# ME433_Spring2017.net
KiCad netlist of a schematic drawn in EAGLE
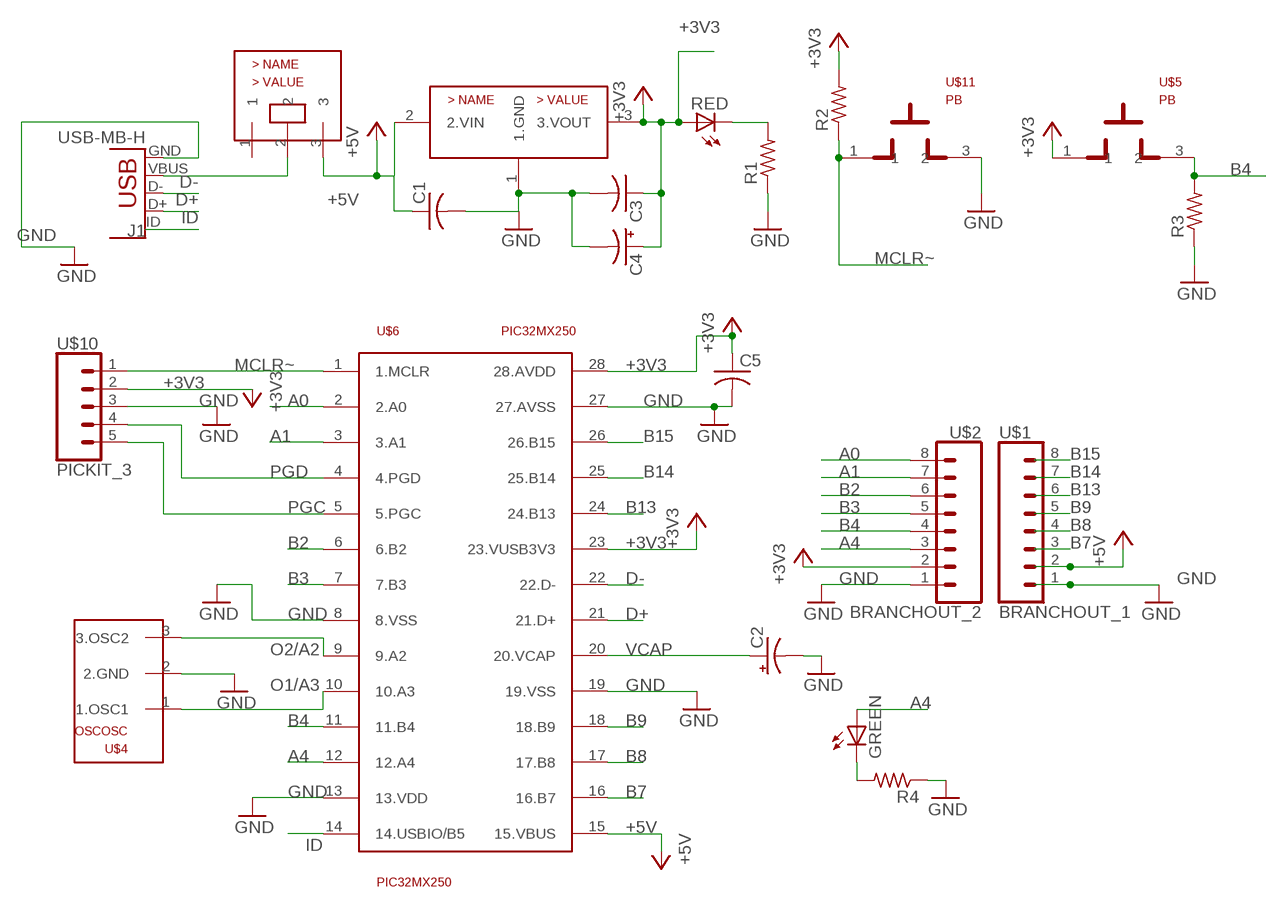
[diagram p0: schematic, sheet 1]

(export (version "E")
  (design (tool "Eeschema 10.0.6"))
  (components
    (comp (ref "C1")
      (value "C-US025-025X050")
      (footprint "eagle-import:C025-025X050")
      (libsource (lib "eagle-import") (part "C-US025-025X050"))
    )
    (comp (ref "C2")
      (value "CPOL-USB45181B")
      (footprint "eagle-import:B45181B")
      (libsource (lib "eagle-import") (part "CPOL-USB45181B"))
    )
    (comp (ref "C3")
      (value "C-US025-025X050")
      (footprint "eagle-import:C025-025X050")
      (libsource (lib "eagle-import") (part "C-US025-025X050"))
    )
    (comp (ref "C4")
      (value "CPOL-USB45181B")
      (footprint "eagle-import:B45181B")
      (libsource (lib "eagle-import") (part "CPOL-USB45181B"))
    )
    (comp (ref "C5")
      (value "C-US025-025X050")
      (footprint "eagle-import:C025-025X050")
      (libsource (lib "eagle-import") (part "C-US025-025X050"))
    )
    (comp (ref "GREEN")
      (value "LED3MM")
      (footprint "eagle-import:LED3MM")
      (libsource (lib "eagle-import") (part "LED3MM"))
    )
    (comp (ref "J1")
      (value "USB-MB-H")
      (footprint "eagle-import:USB-MB-H")
      (libsource (lib "eagle-import") (part "USB-MB-H"))
    )
    (comp (ref "R1")
      (value "R-US_0204/7")
      (footprint "eagle-import:0204_7")
      (libsource (lib "eagle-import") (part "R-US_0204/7"))
    )
    (comp (ref "R2")
      (value "R-US_0204/7")
      (footprint "eagle-import:0204_7")
      (libsource (lib "eagle-import") (part "R-US_0204/7"))
    )
    (comp (ref "R3")
      (value "R-US_0204/7")
      (footprint "eagle-import:0204_7")
      (libsource (lib "eagle-import") (part "R-US_0204/7"))
    )
    (comp (ref "R4")
      (value "R-US_0204/7")
      (footprint "eagle-import:0204_7")
      (libsource (lib "eagle-import") (part "R-US_0204/7"))
    )
    (comp (ref "RED")
      (value "LED3MM")
      (footprint "eagle-import:LED3MM")
      (libsource (lib "eagle-import") (part "LED3MM"))
    )
    (comp (ref "U$1")
      (value "BRANCHOUT_1")
      (footprint "eagle-import:1X08")
      (libsource (lib "eagle-import") (part "BRANCHOUT_1"))
    )
    (comp (ref "U$2")
      (value "BRANCHOUT_2")
      (footprint "eagle-import:1X08")
      (libsource (lib "eagle-import") (part "BRANCHOUT_2"))
    )
    (comp (ref "U$4")
      (value "OSCOSC")
      (footprint "eagle-import:OSC")
      (libsource (lib "eagle-import") (part "OSCOSC"))
    )
    (comp (ref "U$5") (value "PB") (footprint "eagle-import:PB") (libsource (lib "eagle-import") (part "PB")))
    (comp (ref "U$6")
      (value "PIC32MX250")
      (footprint "eagle-import:DIL28-3")
      (libsource (lib "eagle-import") (part "PIC32MX250"))
    )
    (comp (ref "U$8")
      (value "SLIDE")
      (footprint "eagle-import:SLIDE")
      (libsource (lib "eagle-import") (part "SLIDE"))
    )
    (comp (ref "U$10")
      (value "PICKIT_3")
      (footprint "eagle-import:1X05")
      (libsource (lib "eagle-import") (part "PICKIT_3"))
    )
    (comp (ref "U$11")
      (value "PB")
      (footprint "eagle-import:PB")
      (libsource (lib "eagle-import") (part "PB"))
    )
    (comp (ref "_")
      (value "MCP1702")
      (footprint "eagle-import:TO92")
      (libsource (lib "eagle-import") (part "MCP1702"))
    )
  )
  (nets
    (net (code "1") (name "+3V3") (class "Default")
      (node (ref "C3") (pin "1") (pinfunction "1_1") (pintype "passive"))
      (node (ref "C4") (pin "+") (pinfunction "+_+") (pintype "passive"))
      (node (ref "C5") (pin "1") (pinfunction "1_1") (pintype "passive"))
      (node (ref "R2") (pin "2") (pinfunction "2_2") (pintype "passive"))
      (node (ref "RED") (pin "A") (pinfunction "A_A") (pintype "passive"))
      (node (ref "U$10") (pin "2") (pinfunction "2.VDD_2") (pintype "passive"))
      (node (ref "U$2") (pin "2") (pinfunction "2_2") (pintype "passive"))
      (node (ref "U$5") (pin "1") (pinfunction "1_1") (pintype "bidirectional"))
      (node (ref "U$6") (pin "23") (pinfunction "23.VUSB3V3_23") (pintype "bidirectional"))
      (node (ref "U$6") (pin "28") (pinfunction "28.AVDD_28") (pintype "bidirectional"))
      (node (ref "_") (pin "3") (pinfunction "3.VOUT_3") (pintype "bidirectional"))
    )
    (net (code "2") (name "+5V") (class "Default")
      (node (ref "C1") (pin "1") (pinfunction "1_1") (pintype "passive"))
      (node (ref "U$1") (pin "2") (pinfunction "2_2") (pintype "passive"))
      (node (ref "U$6") (pin "15") (pinfunction "15.VBUS_15") (pintype "bidirectional"))
      (node (ref "U$8") (pin "3") (pinfunction "3_3") (pintype "bidirectional"))
      (node (ref "_") (pin "2") (pinfunction "2.VIN_2") (pintype "bidirectional"))
    )
    (net (code "3") (name "/A0") (class "Default")
      (node (ref "U$2") (pin "8") (pinfunction "8_8") (pintype "passive"))
      (node (ref "U$6") (pin "2") (pinfunction "2.A0_2") (pintype "bidirectional"))
    )
    (net (code "4") (name "/A1") (class "Default")
      (node (ref "U$2") (pin "7") (pinfunction "7_7") (pintype "passive"))
      (node (ref "U$6") (pin "3") (pinfunction "3.A1_3") (pintype "bidirectional"))
    )
    (net (code "5") (name "/A4") (class "Default")
      (node (ref "GREEN") (pin "A") (pinfunction "A_A") (pintype "passive"))
      (node (ref "U$2") (pin "3") (pinfunction "3_3") (pintype "passive"))
      (node (ref "U$6") (pin "12") (pinfunction "12.A4_12") (pintype "bidirectional"))
    )
    (net (code "6") (name "/B2") (class "Default")
      (node (ref "U$2") (pin "6") (pinfunction "6_6") (pintype "passive"))
      (node (ref "U$6") (pin "6") (pinfunction "6.B2_6") (pintype "bidirectional"))
    )
    (net (code "7") (name "/B3") (class "Default")
      (node (ref "U$2") (pin "5") (pinfunction "5_5") (pintype "passive"))
      (node (ref "U$6") (pin "7") (pinfunction "7.B3_7") (pintype "bidirectional"))
    )
    (net (code "8") (name "/B4") (class "Default")
      (node (ref "R3") (pin "2") (pinfunction "2_2") (pintype "passive"))
      (node (ref "U$2") (pin "4") (pinfunction "4_4") (pintype "passive"))
      (node (ref "U$5") (pin "3") (pinfunction "2_3") (pintype "bidirectional"))
      (node (ref "U$6") (pin "11") (pinfunction "11.B4_11") (pintype "bidirectional"))
    )
    (net (code "9") (name "/B7") (class "Default")
      (node (ref "U$1") (pin "3") (pinfunction "3_3") (pintype "passive"))
      (node (ref "U$6") (pin "16") (pinfunction "16.B7_16") (pintype "bidirectional"))
    )
    (net (code "10") (name "/B8") (class "Default")
      (node (ref "U$1") (pin "4") (pinfunction "4_4") (pintype "passive"))
      (node (ref "U$6") (pin "17") (pinfunction "17.B8_17") (pintype "bidirectional"))
    )
    (net (code "11") (name "/B9") (class "Default")
      (node (ref "U$1") (pin "5") (pinfunction "5_5") (pintype "passive"))
      (node (ref "U$6") (pin "18") (pinfunction "18.B9_18") (pintype "bidirectional"))
    )
    (net (code "12") (name "/B13") (class "Default")
      (node (ref "U$1") (pin "6") (pinfunction "6_6") (pintype "passive"))
      (node (ref "U$6") (pin "24") (pinfunction "24.B13_24") (pintype "bidirectional"))
    )
    (net (code "13") (name "/B14") (class "Default")
      (node (ref "U$1") (pin "7") (pinfunction "7_7") (pintype "passive"))
      (node (ref "U$6") (pin "25") (pinfunction "25.B14_25") (pintype "bidirectional"))
    )
    (net (code "14") (name "/B15") (class "Default")
      (node (ref "U$1") (pin "8") (pinfunction "8_8") (pintype "passive"))
      (node (ref "U$6") (pin "26") (pinfunction "26.B15_26") (pintype "bidirectional"))
    )
    (net (code "15") (name "/D+") (class "Default")
      (node (ref "J1") (pin "D+") (pinfunction "D+_D+") (pintype "bidirectional"))
      (node (ref "U$6") (pin "21") (pinfunction "21.D+_21") (pintype "bidirectional"))
    )
    (net (code "16") (name "/D-") (class "Default")
      (node (ref "J1") (pin "D-") (pinfunction "D-_D-") (pintype "bidirectional"))
      (node (ref "U$6") (pin "22") (pinfunction "22.D-_22") (pintype "bidirectional"))
    )
    (net (code "17") (name "/ID") (class "Default")
      (node (ref "J1") (pin "ID") (pinfunction "ID_ID") (pintype "bidirectional"))
      (node (ref "U$6") (pin "14") (pinfunction "14.USBIO/B5_14") (pintype "bidirectional"))
    )
    (net (code "18") (name "/MCLR~{}") (class "Default")
      (node (ref "R2") (pin "1") (pinfunction "1_1") (pintype "passive"))
      (node (ref "U$10") (pin "1") (pinfunction "1.MCLR~{}_1") (pintype "passive"))
      (node (ref "U$11") (pin "1") (pinfunction "1_1") (pintype "bidirectional"))
      (node (ref "U$6") (pin "1") (pinfunction "1.MCLR_1") (pintype "bidirectional"))
    )
    (net (code "19") (name "/O1{slash}A3") (class "Default")
      (node (ref "U$4") (pin "1") (pinfunction "1.OSC1_1") (pintype "bidirectional"))
      (node (ref "U$6") (pin "10") (pinfunction "10.A3_10") (pintype "bidirectional"))
    )
    (net (code "20") (name "/O2{slash}A2") (class "Default")
      (node (ref "U$4") (pin "3") (pinfunction "3.OSC2_3") (pintype "bidirectional"))
      (node (ref "U$6") (pin "9") (pinfunction "9.A2_9") (pintype "bidirectional"))
    )
    (net (code "21") (name "/PGC") (class "Default")
      (node (ref "U$10") (pin "5") (pinfunction "5.PGC_5") (pintype "passive"))
      (node (ref "U$6") (pin "5") (pinfunction "5.PGC_5") (pintype "bidirectional"))
    )
    (net (code "22") (name "/PGD") (class "Default")
      (node (ref "U$10") (pin "4") (pinfunction "4.PGD_4") (pintype "passive"))
      (node (ref "U$6") (pin "4") (pinfunction "4.PGD_4") (pintype "bidirectional"))
    )
    (net (code "23") (name "/VCAP") (class "Default")
      (node (ref "C2") (pin "+") (pinfunction "+_+") (pintype "passive"))
      (node (ref "U$6") (pin "20") (pinfunction "20.VCAP_20") (pintype "bidirectional"))
    )
    (net (code "24") (name "GND") (class "Default")
      (node (ref "C1") (pin "2") (pinfunction "2_2") (pintype "passive"))
      (node (ref "C2") (pin "-") (pinfunction "-_-") (pintype "passive"))
      (node (ref "C3") (pin "2") (pinfunction "2_2") (pintype "passive"))
      (node (ref "C4") (pin "-") (pinfunction "-_-") (pintype "passive"))
      (node (ref "C5") (pin "2") (pinfunction "2_2") (pintype "passive"))
      (node (ref "J1") (pin "GND") (pinfunction "GND_GND") (pintype "bidirectional"))
      (node (ref "R1") (pin "1") (pinfunction "1_1") (pintype "passive"))
      (node (ref "R3") (pin "1") (pinfunction "1_1") (pintype "passive"))
      (node (ref "R4") (pin "1") (pinfunction "1_1") (pintype "passive"))
      (node (ref "U$1") (pin "1") (pinfunction "1_1") (pintype "passive"))
      (node (ref "U$10") (pin "3") (pinfunction "3.VSS_3") (pintype "passive"))
      (node (ref "U$11") (pin "3") (pinfunction "2_3") (pintype "bidirectional"))
      (node (ref "U$2") (pin "1") (pinfunction "1_1") (pintype "passive"))
      (node (ref "U$4") (pin "2") (pinfunction "2.GND_2") (pintype "bidirectional"))
      (node (ref "U$6") (pin "13") (pinfunction "13.VDD_13") (pintype "bidirectional"))
      (node (ref "U$6") (pin "19") (pinfunction "19.VSS_19") (pintype "bidirectional"))
      (node (ref "U$6") (pin "27") (pinfunction "27.AVSS_27") (pintype "bidirectional"))
      (node (ref "U$6") (pin "8") (pinfunction "8.VSS_8") (pintype "bidirectional"))
      (node (ref "_") (pin "1") (pinfunction "1.GND_1") (pintype "bidirectional"))
    )
    (net (code "25") (name "Net-(GREEN-C)") (class "Default")
      (node (ref "GREEN") (pin "K") (pinfunction "C_K") (pintype "passive"))
      (node (ref "R4") (pin "2") (pinfunction "2_2") (pintype "passive"))
    )
    (net (code "26") (name "Net-(J1-PadVBUS)") (class "Default")
      (node (ref "J1") (pin "VBUS") (pinfunction "VBUS_VBUS") (pintype "bidirectional"))
      (node (ref "U$8") (pin "2") (pinfunction "2_2") (pintype "bidirectional"))
    )
    (net (code "27") (name "Net-(RED-C)") (class "Default")
      (node (ref "R1") (pin "2") (pinfunction "2_2") (pintype "passive"))
      (node (ref "RED") (pin "K") (pinfunction "C_K") (pintype "passive"))
    )
    (net (code "28") (name "unconnected-(U$8-Pad1)") (class "Default")
      (node (ref "U$8") (pin "1") (pinfunction "1_1") (pintype "bidirectional"))
    )
  )
)
